# G223D.net
KiCad netlist of a schematic drawn in EAGLE
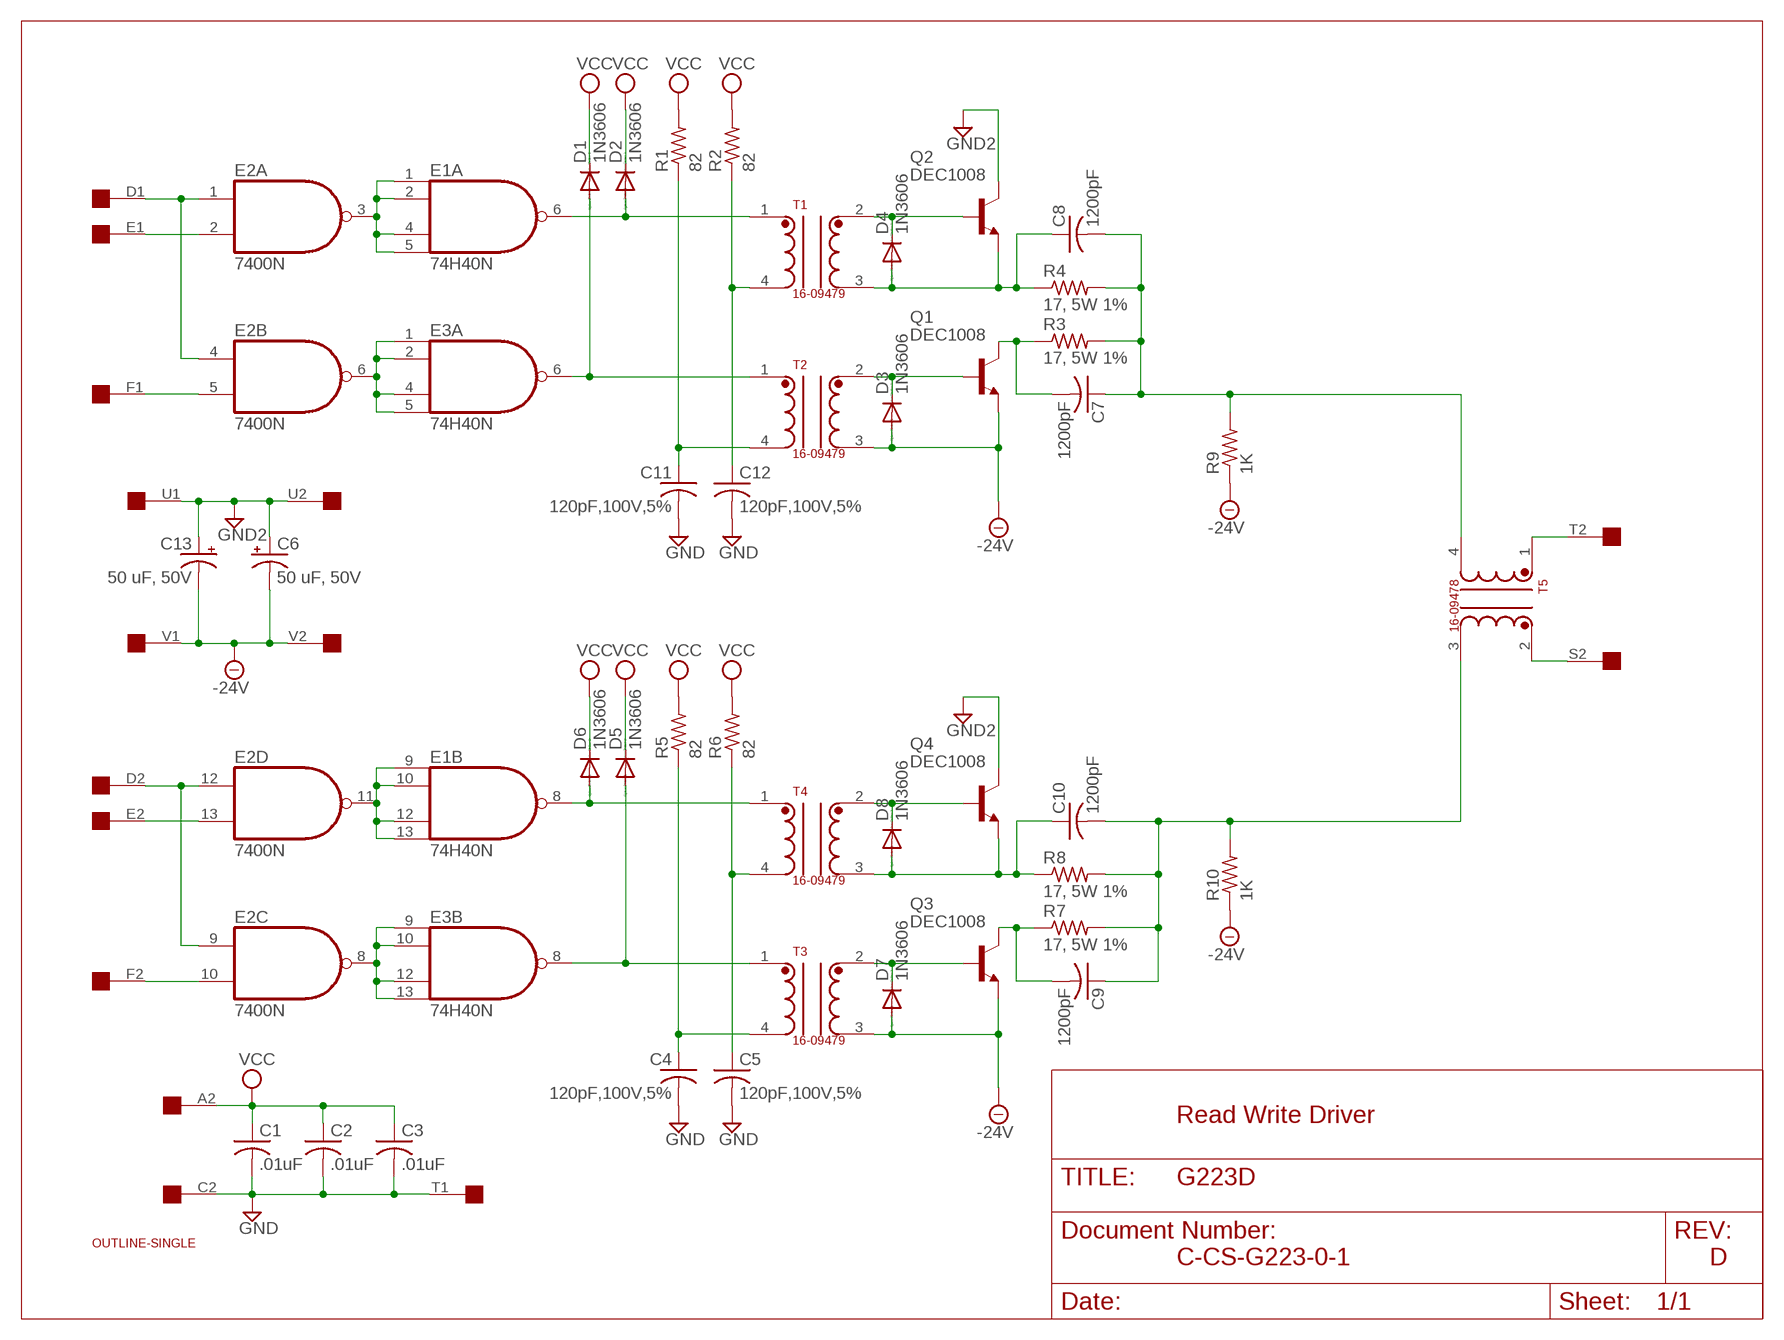
[diagram p0: schematic, sheet 1]

(export (version "E")
  (design (tool "Eeschema 10.0.6"))
  (components
    (comp (ref "C1")
      (value ".01uF")
      (footprint "eagle-import:C050-025X075")
      (libsource (lib "eagle-import") (part "C-US050-025X075"))
    )
    (comp (ref "C2")
      (value ".01uF")
      (footprint "eagle-import:C050-025X075")
      (libsource (lib "eagle-import") (part "C-US050-025X075"))
    )
    (comp (ref "C3")
      (value ".01uF")
      (footprint "eagle-import:C050-025X075")
      (libsource (lib "eagle-import") (part "C-US050-025X075"))
    )
    (comp (ref "C4")
      (value "120pF,100V,5%")
      (footprint "eagle-import:C075-032X103")
      (libsource (lib "eagle-import") (part "C-US075-032X103"))
    )
    (comp (ref "C5")
      (value "120pF,100V,5%")
      (footprint "eagle-import:C075-032X103")
      (libsource (lib "eagle-import") (part "C-US075-032X103"))
    )
    (comp (ref "C6")
      (value "50 uF, 50V")
      (footprint "eagle-import:E30-10")
      (libsource (lib "eagle-import") (part "CPOL-USE30-10AXIAL"))
    )
    (comp (ref "C7")
      (value "1200pF")
      (footprint "eagle-import:C075-032X103")
      (libsource (lib "eagle-import") (part "C-US075-032X103"))
    )
    (comp (ref "C8")
      (value "1200pF")
      (footprint "eagle-import:C075-032X103")
      (libsource (lib "eagle-import") (part "C-US075-032X103"))
    )
    (comp (ref "C9")
      (value "1200pF")
      (footprint "eagle-import:C075-032X103")
      (libsource (lib "eagle-import") (part "C-US075-032X103"))
    )
    (comp (ref "C10")
      (value "1200pF")
      (footprint "eagle-import:C075-032X103")
      (libsource (lib "eagle-import") (part "C-US075-032X103"))
    )
    (comp (ref "C11")
      (value "120pF,100V,5%")
      (footprint "eagle-import:C075-032X103")
      (libsource (lib "eagle-import") (part "C-US075-032X103"))
    )
    (comp (ref "C12")
      (value "120pF,100V,5%")
      (footprint "eagle-import:C075-032X103")
      (libsource (lib "eagle-import") (part "C-US075-032X103"))
    )
    (comp (ref "C13")
      (value "50 uF, 50V")
      (footprint "eagle-import:E30-10")
      (libsource (lib "eagle-import") (part "CPOL-USE30-10AXIAL"))
    )
    (comp (ref "D1")
      (value "1N3606")
      (footprint "eagle-import:DO35-10")
      (libsource (lib "eagle-import") (part "DIODE-DO35-10"))
    )
    (comp (ref "D2")
      (value "1N3606")
      (footprint "eagle-import:DO35-10")
      (libsource (lib "eagle-import") (part "DIODE-DO35-10"))
    )
    (comp (ref "D3")
      (value "1N3606")
      (footprint "eagle-import:DO35-10")
      (libsource (lib "eagle-import") (part "DIODE-DO35-10"))
    )
    (comp (ref "D4")
      (value "1N3606")
      (footprint "eagle-import:DO35-10")
      (libsource (lib "eagle-import") (part "DIODE-DO35-10"))
    )
    (comp (ref "D5")
      (value "1N3606")
      (footprint "eagle-import:DO35-10")
      (libsource (lib "eagle-import") (part "DIODE-DO35-10"))
    )
    (comp (ref "D6")
      (value "1N3606")
      (footprint "eagle-import:DO35-10")
      (libsource (lib "eagle-import") (part "DIODE-DO35-10"))
    )
    (comp (ref "D7")
      (value "1N3606")
      (footprint "eagle-import:DO35-10")
      (libsource (lib "eagle-import") (part "DIODE-DO35-10"))
    )
    (comp (ref "D8")
      (value "1N3606")
      (footprint "eagle-import:DO35-10")
      (libsource (lib "eagle-import") (part "DIODE-DO35-10"))
    )
    (comp (ref "E1")
      (value "74H40N")
      (footprint "eagle-import:DIL14")
      (libsource (lib "eagle-import") (part "7440NS"))
    )
    (comp (ref "E2")
      (value "7400N")
      (footprint "eagle-import:DIL14")
      (libsource (lib "eagle-import") (part "7400N"))
    )
    (comp (ref "E3")
      (value "74H40N")
      (footprint "eagle-import:DIL14")
      (libsource (lib "eagle-import") (part "7440NS"))
    )
    (comp (ref "EDGE1")
      (value "EDGE-2CONNECTOR")
      (footprint "eagle-import:EDGE-CON2")
      (libsource (lib "eagle-import") (part "EDGE-2CONNECTOR"))
    )
    (comp (ref "Q1")
      (value "DEC1008")
      (footprint "eagle-import:TO5")
      (libsource (lib "eagle-import") (part "-NPN-TO5"))
    )
    (comp (ref "Q2")
      (value "DEC1008")
      (footprint "eagle-import:TO5")
      (libsource (lib "eagle-import") (part "-NPN-TO5"))
    )
    (comp (ref "Q3")
      (value "DEC1008")
      (footprint "eagle-import:TO5")
      (libsource (lib "eagle-import") (part "-NPN-TO5"))
    )
    (comp (ref "Q4")
      (value "DEC1008")
      (footprint "eagle-import:TO5")
      (libsource (lib "eagle-import") (part "-NPN-TO5"))
    )
    (comp (ref "R1")
      (value "82")
      (footprint "eagle-import:0207_10")
      (libsource (lib "eagle-import") (part "R-US_0207/10"))
    )
    (comp (ref "R2")
      (value "82")
      (footprint "eagle-import:0207_10")
      (libsource (lib "eagle-import") (part "R-US_0207/10"))
    )
    (comp (ref "R3")
      (value "17, 5W 1%")
      (footprint "eagle-import:VTA52")
      (libsource (lib "eagle-import") (part "R-US_VTA52"))
    )
    (comp (ref "R4")
      (value "17, 5W 1%")
      (footprint "eagle-import:VTA52")
      (libsource (lib "eagle-import") (part "R-US_VTA52"))
    )
    (comp (ref "R5")
      (value "82")
      (footprint "eagle-import:0207_10")
      (libsource (lib "eagle-import") (part "R-US_0207/10"))
    )
    (comp (ref "R6")
      (value "82")
      (footprint "eagle-import:0207_10")
      (libsource (lib "eagle-import") (part "R-US_0207/10"))
    )
    (comp (ref "R7")
      (value "17, 5W 1%")
      (footprint "eagle-import:VTA52")
      (libsource (lib "eagle-import") (part "R-US_VTA52"))
    )
    (comp (ref "R8")
      (value "17, 5W 1%")
      (footprint "eagle-import:VTA52")
      (libsource (lib "eagle-import") (part "R-US_VTA52"))
    )
    (comp (ref "R9")
      (value "1K")
      (footprint "eagle-import:0207_10")
      (libsource (lib "eagle-import") (part "R-US_0207/10"))
    )
    (comp (ref "R10")
      (value "1K")
      (footprint "eagle-import:0207_10")
      (libsource (lib "eagle-import") (part "R-US_0207/10"))
    )
    (comp (ref "T1")
      (value "16-09479")
      (footprint "eagle-import:TRANSFORMER-SIL4")
      (libsource (lib "eagle-import") (part "16-09479"))
    )
    (comp (ref "T2")
      (value "16-09479")
      (footprint "eagle-import:TRANSFORMER-SIL4")
      (libsource (lib "eagle-import") (part "16-09479"))
    )
    (comp (ref "T3")
      (value "16-09479")
      (footprint "eagle-import:TRANSFORMER-SIL4")
      (libsource (lib "eagle-import") (part "16-09479"))
    )
    (comp (ref "T4")
      (value "16-09479")
      (footprint "eagle-import:TRANSFORMER-SIL4")
      (libsource (lib "eagle-import") (part "16-09479"))
    )
    (comp (ref "T5")
      (value "16-09478")
      (footprint "eagle-import:TRANSFORMER-SIL4")
      (libsource (lib "eagle-import") (part "16-09479"))
    )
    (comp (ref "U$1")
      (value "OUTLINE-SINGLE")
      (footprint "eagle-import:SINGLE")
      (libsource (lib "eagle-import") (part "OUTLINE-SINGLE"))
    )
  )
  (nets
    (net (code "1") (name "-24V") (class "Default")
      (node (ref "C13") (pin "-") (pinfunction "-_-") (pintype "passive"))
      (node (ref "C6") (pin "-") (pinfunction "-_-") (pintype "passive"))
      (node (ref "D3") (pin "A") (pinfunction "A_A") (pintype "passive"))
      (node (ref "D7") (pin "A") (pinfunction "A_A") (pintype "passive"))
      (node (ref "EDGE1") (pin "V1") (pinfunction "1_V1") (pintype "bidirectional"))
      (node (ref "EDGE1") (pin "V2") (pinfunction "1_V2") (pintype "bidirectional"))
      (node (ref "Q1") (pin "1") (pinfunction "E_1") (pintype "passive"))
      (node (ref "Q3") (pin "1") (pinfunction "E_1") (pintype "passive"))
      (node (ref "R10") (pin "1") (pinfunction "1_1") (pintype "passive"))
      (node (ref "R9") (pin "1") (pinfunction "1_1") (pintype "passive"))
      (node (ref "T2") (pin "3") (pinfunction "P$5_3") (pintype "passive"))
      (node (ref "T3") (pin "3") (pinfunction "P$5_3") (pintype "passive"))
    )
    (net (code "2") (name "GND") (class "Default")
      (node (ref "C1") (pin "2") (pinfunction "2_2") (pintype "passive"))
      (node (ref "C11") (pin "2") (pinfunction "2_2") (pintype "passive"))
      (node (ref "C12") (pin "2") (pinfunction "2_2") (pintype "passive"))
      (node (ref "C2") (pin "2") (pinfunction "2_2") (pintype "passive"))
      (node (ref "C3") (pin "2") (pinfunction "2_2") (pintype "passive"))
      (node (ref "C4") (pin "2") (pinfunction "2_2") (pintype "passive"))
      (node (ref "C5") (pin "2") (pinfunction "2_2") (pintype "passive"))
      (node (ref "EDGE1") (pin "C2") (pinfunction "1_C2") (pintype "bidirectional"))
      (node (ref "EDGE1") (pin "T1") (pinfunction "1_T1") (pintype "bidirectional"))
    )
    (net (code "3") (name "GND2") (class "Default")
      (node (ref "C13") (pin "+") (pinfunction "+_+") (pintype "passive"))
      (node (ref "C6") (pin "+") (pinfunction "+_+") (pintype "passive"))
      (node (ref "EDGE1") (pin "U1") (pinfunction "1_U1") (pintype "bidirectional"))
      (node (ref "EDGE1") (pin "U2") (pinfunction "1_U2") (pintype "bidirectional"))
      (node (ref "Q2") (pin "3") (pinfunction "C_3") (pintype "passive"))
      (node (ref "Q4") (pin "3") (pinfunction "C_3") (pintype "passive"))
    )
    (net (code "4") (name "Net-(E1C-I0)") (class "Default")
      (node (ref "E1") (pin "1") (pinfunction "I0_1") (pintype "input"))
      (node (ref "E1") (pin "2") (pinfunction "I1_2") (pintype "input"))
      (node (ref "E1") (pin "4") (pinfunction "I2_4") (pintype "input"))
      (node (ref "E1") (pin "5") (pinfunction "I3_5") (pintype "input"))
      (node (ref "E2") (pin "3") (pinfunction "O_3") (pintype "output"))
    )
    (net (code "5") (name "Net-(E1C-O)") (class "Default")
      (node (ref "D2") (pin "A") (pinfunction "A_A") (pintype "passive"))
      (node (ref "E1") (pin "6") (pinfunction "O_6") (pintype "output"))
      (node (ref "T1") (pin "1") (pinfunction "P$2_1") (pintype "passive"))
    )
    (net (code "6") (name "Net-(E1D-I0)") (class "Default")
      (node (ref "E1") (pin "10") (pinfunction "I1_10") (pintype "input"))
      (node (ref "E1") (pin "12") (pinfunction "I2_12") (pintype "input"))
      (node (ref "E1") (pin "13") (pinfunction "I3_13") (pintype "input"))
      (node (ref "E1") (pin "9") (pinfunction "I0_9") (pintype "input"))
      (node (ref "E2") (pin "11") (pinfunction "O_11") (pintype "output"))
    )
    (net (code "7") (name "Net-(E1D-O)") (class "Default")
      (node (ref "D6") (pin "A") (pinfunction "A_A") (pintype "passive"))
      (node (ref "E1") (pin "8") (pinfunction "O_8") (pintype "output"))
      (node (ref "T4") (pin "1") (pinfunction "P$2_1") (pintype "passive"))
    )
    (net (code "8") (name "Net-(E2A-I0)") (class "Default")
      (node (ref "E2") (pin "1") (pinfunction "I0_1") (pintype "input"))
      (node (ref "E2") (pin "4") (pinfunction "I0_4") (pintype "input"))
      (node (ref "EDGE1") (pin "D1") (pinfunction "1_D1") (pintype "bidirectional"))
    )
    (net (code "9") (name "Net-(E2A-I1)") (class "Default")
      (node (ref "E2") (pin "2") (pinfunction "I1_2") (pintype "input"))
      (node (ref "EDGE1") (pin "E1") (pinfunction "1_E1") (pintype "bidirectional"))
    )
    (net (code "10") (name "Net-(E2B-I1)") (class "Default")
      (node (ref "E2") (pin "5") (pinfunction "I1_5") (pintype "input"))
      (node (ref "EDGE1") (pin "F1") (pinfunction "1_F1") (pintype "bidirectional"))
    )
    (net (code "11") (name "Net-(E2B-O)") (class "Default")
      (node (ref "E2") (pin "6") (pinfunction "O_6") (pintype "output"))
      (node (ref "E3") (pin "1") (pinfunction "I0_1") (pintype "input"))
      (node (ref "E3") (pin "2") (pinfunction "I1_2") (pintype "input"))
      (node (ref "E3") (pin "4") (pinfunction "I2_4") (pintype "input"))
      (node (ref "E3") (pin "5") (pinfunction "I3_5") (pintype "input"))
    )
    (net (code "12") (name "Net-(E2C-I0)") (class "Default")
      (node (ref "E2") (pin "12") (pinfunction "I0_12") (pintype "input"))
      (node (ref "E2") (pin "9") (pinfunction "I0_9") (pintype "input"))
      (node (ref "EDGE1") (pin "D2") (pinfunction "1_D2") (pintype "bidirectional"))
    )
    (net (code "13") (name "Net-(E2C-I1)") (class "Default")
      (node (ref "E2") (pin "10") (pinfunction "I1_10") (pintype "input"))
      (node (ref "EDGE1") (pin "F2") (pinfunction "1_F2") (pintype "bidirectional"))
    )
    (net (code "14") (name "Net-(E2C-O)") (class "Default")
      (node (ref "E2") (pin "8") (pinfunction "O_8") (pintype "output"))
      (node (ref "E3") (pin "10") (pinfunction "I1_10") (pintype "input"))
      (node (ref "E3") (pin "12") (pinfunction "I2_12") (pintype "input"))
      (node (ref "E3") (pin "13") (pinfunction "I3_13") (pintype "input"))
      (node (ref "E3") (pin "9") (pinfunction "I0_9") (pintype "input"))
    )
    (net (code "15") (name "Net-(E2D-I1)") (class "Default")
      (node (ref "E2") (pin "13") (pinfunction "I1_13") (pintype "input"))
      (node (ref "EDGE1") (pin "E2") (pinfunction "1_E2") (pintype "bidirectional"))
    )
    (net (code "16") (name "Net-(E3C-O)") (class "Default")
      (node (ref "D1") (pin "A") (pinfunction "A_A") (pintype "passive"))
      (node (ref "E3") (pin "6") (pinfunction "O_6") (pintype "output"))
      (node (ref "T2") (pin "1") (pinfunction "P$2_1") (pintype "passive"))
    )
    (net (code "17") (name "Net-(E3D-O)") (class "Default")
      (node (ref "D5") (pin "A") (pinfunction "A_A") (pintype "passive"))
      (node (ref "E3") (pin "8") (pinfunction "O_8") (pintype "output"))
      (node (ref "T3") (pin "1") (pinfunction "P$2_1") (pintype "passive"))
    )
    (net (code "18") (name "Net-(EDGE1AD-1)") (class "Default")
      (node (ref "EDGE1") (pin "S2") (pinfunction "1_S2") (pintype "bidirectional"))
      (node (ref "T5") (pin "2") (pinfunction "P$4_2") (pintype "passive"))
    )
    (net (code "19") (name "Net-(EDGE1AF-1)") (class "Default")
      (node (ref "EDGE1") (pin "T2") (pinfunction "1_T2") (pintype "bidirectional"))
      (node (ref "T5") (pin "1") (pinfunction "P$2_1") (pintype "passive"))
    )
    (net (code "20") (name "Net-(Q1-B)") (class "Default")
      (node (ref "D3") (pin "C") (pinfunction "C_C") (pintype "passive"))
      (node (ref "Q1") (pin "2") (pinfunction "B_2") (pintype "passive"))
      (node (ref "T2") (pin "2") (pinfunction "P$4_2") (pintype "passive"))
    )
    (net (code "21") (name "Net-(Q1-C)") (class "Default")
      (node (ref "C7") (pin "2") (pinfunction "2_2") (pintype "passive"))
      (node (ref "Q1") (pin "3") (pinfunction "C_3") (pintype "passive"))
      (node (ref "R3") (pin "1") (pinfunction "1_1") (pintype "passive"))
    )
    (net (code "22") (name "Net-(Q2-B)") (class "Default")
      (node (ref "D4") (pin "C") (pinfunction "C_C") (pintype "passive"))
      (node (ref "Q2") (pin "2") (pinfunction "B_2") (pintype "passive"))
      (node (ref "T1") (pin "2") (pinfunction "P$4_2") (pintype "passive"))
    )
    (net (code "23") (name "Net-(Q2-E)") (class "Default")
      (node (ref "C8") (pin "1") (pinfunction "1_1") (pintype "passive"))
      (node (ref "D4") (pin "A") (pinfunction "A_A") (pintype "passive"))
      (node (ref "Q2") (pin "1") (pinfunction "E_1") (pintype "passive"))
      (node (ref "R4") (pin "1") (pinfunction "1_1") (pintype "passive"))
      (node (ref "T1") (pin "3") (pinfunction "P$5_3") (pintype "passive"))
    )
    (net (code "24") (name "Net-(Q3-B)") (class "Default")
      (node (ref "D7") (pin "C") (pinfunction "C_C") (pintype "passive"))
      (node (ref "Q3") (pin "2") (pinfunction "B_2") (pintype "passive"))
      (node (ref "T3") (pin "2") (pinfunction "P$4_2") (pintype "passive"))
    )
    (net (code "25") (name "Net-(Q3-C)") (class "Default")
      (node (ref "C9") (pin "2") (pinfunction "2_2") (pintype "passive"))
      (node (ref "Q3") (pin "3") (pinfunction "C_3") (pintype "passive"))
      (node (ref "R7") (pin "1") (pinfunction "1_1") (pintype "passive"))
    )
    (net (code "26") (name "Net-(Q4-B)") (class "Default")
      (node (ref "D8") (pin "C") (pinfunction "C_C") (pintype "passive"))
      (node (ref "Q4") (pin "2") (pinfunction "B_2") (pintype "passive"))
      (node (ref "T4") (pin "2") (pinfunction "P$4_2") (pintype "passive"))
    )
    (net (code "27") (name "Net-(Q4-E)") (class "Default")
      (node (ref "C10") (pin "1") (pinfunction "1_1") (pintype "passive"))
      (node (ref "D8") (pin "A") (pinfunction "A_A") (pintype "passive"))
      (node (ref "Q4") (pin "1") (pinfunction "E_1") (pintype "passive"))
      (node (ref "R8") (pin "1") (pinfunction "1_1") (pintype "passive"))
      (node (ref "T4") (pin "3") (pinfunction "P$5_3") (pintype "passive"))
    )
    (net (code "28") (name "Net-(T1-P$7)") (class "Default")
      (node (ref "C12") (pin "1") (pinfunction "1_1") (pintype "passive"))
      (node (ref "R2") (pin "1") (pinfunction "1_1") (pintype "passive"))
      (node (ref "T1") (pin "4") (pinfunction "P$7_4") (pintype "passive"))
    )
    (net (code "29") (name "Net-(T2-P$7)") (class "Default")
      (node (ref "C11") (pin "1") (pinfunction "1_1") (pintype "passive"))
      (node (ref "R1") (pin "1") (pinfunction "1_1") (pintype "passive"))
      (node (ref "T2") (pin "4") (pinfunction "P$7_4") (pintype "passive"))
    )
    (net (code "30") (name "Net-(T3-P$7)") (class "Default")
      (node (ref "C4") (pin "1") (pinfunction "1_1") (pintype "passive"))
      (node (ref "R5") (pin "1") (pinfunction "1_1") (pintype "passive"))
      (node (ref "T3") (pin "4") (pinfunction "P$7_4") (pintype "passive"))
    )
    (net (code "31") (name "Net-(T4-P$7)") (class "Default")
      (node (ref "C5") (pin "1") (pinfunction "1_1") (pintype "passive"))
      (node (ref "R6") (pin "1") (pinfunction "1_1") (pintype "passive"))
      (node (ref "T4") (pin "4") (pinfunction "P$7_4") (pintype "passive"))
    )
    (net (code "32") (name "Net-(T5-P$5)") (class "Default")
      (node (ref "C10") (pin "2") (pinfunction "2_2") (pintype "passive"))
      (node (ref "C9") (pin "1") (pinfunction "1_1") (pintype "passive"))
      (node (ref "R10") (pin "2") (pinfunction "2_2") (pintype "passive"))
      (node (ref "R7") (pin "2") (pinfunction "2_2") (pintype "passive"))
      (node (ref "R8") (pin "2") (pinfunction "2_2") (pintype "passive"))
      (node (ref "T5") (pin "3") (pinfunction "P$5_3") (pintype "passive"))
    )
    (net (code "33") (name "Net-(T5-P$7)") (class "Default")
      (node (ref "C7") (pin "1") (pinfunction "1_1") (pintype "passive"))
      (node (ref "C8") (pin "2") (pinfunction "2_2") (pintype "passive"))
      (node (ref "R3") (pin "2") (pinfunction "2_2") (pintype "passive"))
      (node (ref "R4") (pin "2") (pinfunction "2_2") (pintype "passive"))
      (node (ref "R9") (pin "2") (pinfunction "2_2") (pintype "passive"))
      (node (ref "T5") (pin "4") (pinfunction "P$7_4") (pintype "passive"))
    )
    (net (code "34") (name "VCC") (class "Default")
      (node (ref "C1") (pin "1") (pinfunction "1_1") (pintype "passive"))
      (node (ref "C2") (pin "1") (pinfunction "1_1") (pintype "passive"))
      (node (ref "C3") (pin "1") (pinfunction "1_1") (pintype "passive"))
      (node (ref "D1") (pin "C") (pinfunction "C_C") (pintype "passive"))
      (node (ref "D2") (pin "C") (pinfunction "C_C") (pintype "passive"))
      (node (ref "D5") (pin "C") (pinfunction "C_C") (pintype "passive"))
      (node (ref "D6") (pin "C") (pinfunction "C_C") (pintype "passive"))
      (node (ref "EDGE1") (pin "A2") (pinfunction "1_A2") (pintype "bidirectional"))
      (node (ref "R1") (pin "2") (pinfunction "2_2") (pintype "passive"))
      (node (ref "R2") (pin "2") (pinfunction "2_2") (pintype "passive"))
      (node (ref "R5") (pin "2") (pinfunction "2_2") (pintype "passive"))
      (node (ref "R6") (pin "2") (pinfunction "2_2") (pintype "passive"))
    )
  )
)
